# HW1_22.net
KiCad netlist of a schematic drawn in EasyEDA
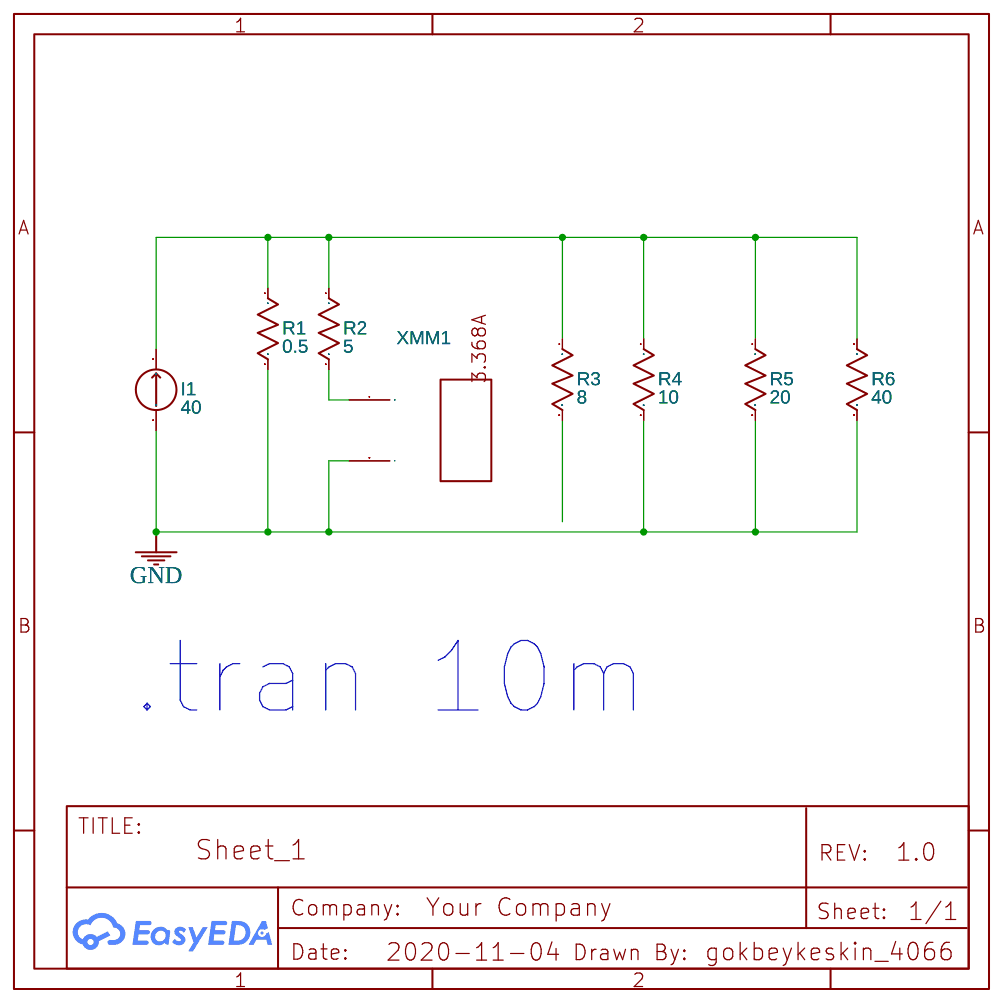
[diagram p0: schematic sheet]

(export (version "E")
  (design (tool "Eeschema 10.0.6"))
  (components
    (comp (ref "I1") (value "40") (libsource (lib "") (part "IDC")))
    (comp (ref "R1") (value "0.5") (libsource (lib "") (part "Resistor_US")))
    (comp (ref "R2") (value "5") (libsource (lib "") (part "Resistor_US")))
    (comp (ref "R3") (value "8") (libsource (lib "") (part "Resistor_US")))
    (comp (ref "R4") (value "10") (libsource (lib "") (part "Resistor_US")))
    (comp (ref "R5") (value "20") (libsource (lib "") (part "Resistor_US")))
    (comp (ref "R6") (value "40") (libsource (lib "") (part "Resistor_US")))
    (comp (ref "XMM1") (value "Multimeter") (libsource (lib "") (part "MULTIMETER")))
  )
  (nets
    (net (code "1") (name "GND") (class "Default")
      (node (ref "I1") (pin "1") (pinfunction "1_1") (pintype "unspecified"))
      (node (ref "R1") (pin "2") (pinfunction "2_2") (pintype "unspecified"))
      (node (ref "R4") (pin "2") (pinfunction "2_2") (pintype "unspecified"))
      (node (ref "R5") (pin "2") (pinfunction "2_2") (pintype "unspecified"))
      (node (ref "R6") (pin "2") (pinfunction "2_2") (pintype "unspecified"))
      (node (ref "XMM1") (pin "2") (pinfunction "I_2") (pintype "unspecified"))
    )
    (net (code "2") (name "Net-(I1-Pad2)") (class "Default")
      (node (ref "I1") (pin "2") (pinfunction "2_2") (pintype "unspecified"))
      (node (ref "R1") (pin "1") (pinfunction "1_1") (pintype "unspecified"))
      (node (ref "R2") (pin "1") (pinfunction "1_1") (pintype "unspecified"))
      (node (ref "R3") (pin "1") (pinfunction "1_1") (pintype "unspecified"))
      (node (ref "R4") (pin "1") (pinfunction "1_1") (pintype "unspecified"))
      (node (ref "R5") (pin "1") (pinfunction "1_1") (pintype "unspecified"))
      (node (ref "R6") (pin "1") (pinfunction "1_1") (pintype "unspecified"))
    )
    (net (code "3") (name "Net-(XMM1-+)") (class "Default")
      (node (ref "R2") (pin "2") (pinfunction "2_2") (pintype "unspecified"))
      (node (ref "XMM1") (pin "1") (pinfunction "+_1") (pintype "unspecified"))
    )
    (net (code "4") (name "unconnected-(R3-Pad2)") (class "Default")
      (node (ref "R3") (pin "2") (pinfunction "2_2") (pintype "unspecified"))
    )
  )
)
